# tako.net
KiCad netlist of a schematic drawn in EAGLE
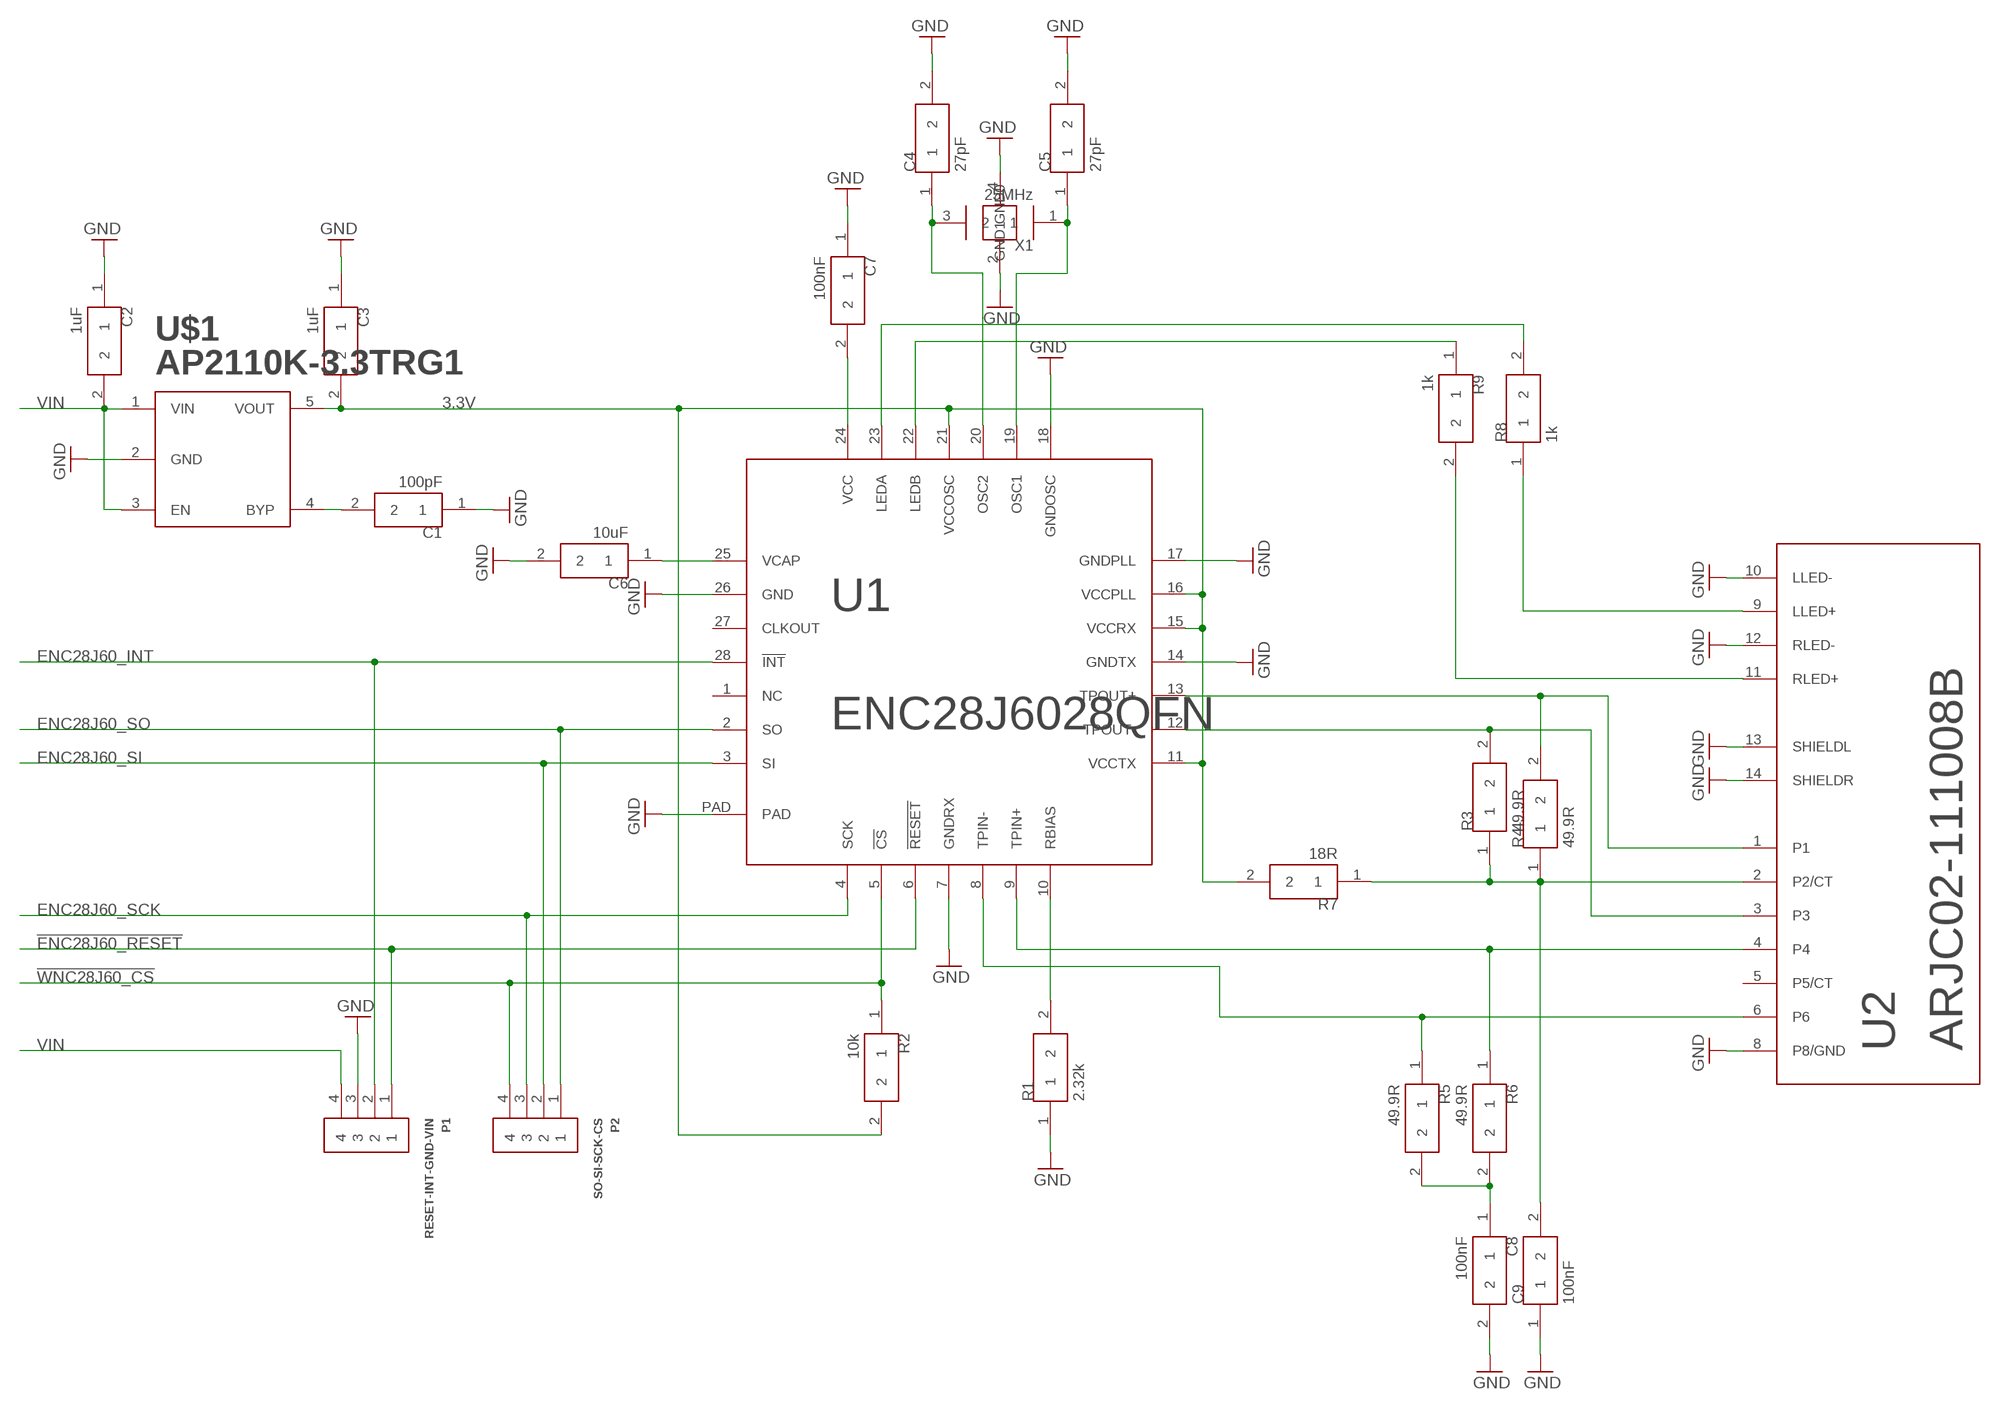
[diagram p0: schematic, sheet 1]

(export (version "E")
  (design (tool "Eeschema 10.0.6"))
  (components
    (comp (ref "C1")
      (value "100pF")
      (footprint "eagle-import:0805")
      (libsource (lib "eagle-import") (part "CAP0805"))
    )
    (comp (ref "C2")
      (value "1uF")
      (footprint "eagle-import:0805")
      (libsource (lib "eagle-import") (part "CAP0805"))
    )
    (comp (ref "C3")
      (value "1uF")
      (footprint "eagle-import:0805")
      (libsource (lib "eagle-import") (part "CAP0805"))
    )
    (comp (ref "C4")
      (value "27pF")
      (footprint "eagle-import:0805")
      (libsource (lib "eagle-import") (part "CAP0805"))
    )
    (comp (ref "C5")
      (value "27pF")
      (footprint "eagle-import:0805")
      (libsource (lib "eagle-import") (part "CAP0805"))
    )
    (comp (ref "C6")
      (value "10uF")
      (footprint "eagle-import:0805")
      (libsource (lib "eagle-import") (part "CAP0805"))
    )
    (comp (ref "C7")
      (value "100nF")
      (footprint "eagle-import:0805")
      (libsource (lib "eagle-import") (part "CAP0805"))
    )
    (comp (ref "C8")
      (value "100nF")
      (footprint "eagle-import:0805")
      (libsource (lib "eagle-import") (part "CAP0805"))
    )
    (comp (ref "C9")
      (value "100nF")
      (footprint "eagle-import:0805")
      (libsource (lib "eagle-import") (part "CAP0805"))
    )
    (comp (ref "P1")
      (value "RESET-INT-GND-VIN")
      (footprint "eagle-import:PIN_4")
      (libsource (lib "eagle-import") (part "PIN_4"))
    )
    (comp (ref "P2")
      (value "SO-SI-SCK-CS")
      (footprint "eagle-import:PIN_4")
      (libsource (lib "eagle-import") (part "PIN_4"))
    )
    (comp (ref "R1")
      (value "2.32k")
      (footprint "eagle-import:0805")
      (libsource (lib "eagle-import") (part "RES0805"))
    )
    (comp (ref "R2")
      (value "10k")
      (footprint "eagle-import:0805")
      (libsource (lib "eagle-import") (part "RES0805"))
    )
    (comp (ref "R3")
      (value "49.9R")
      (footprint "eagle-import:0805")
      (libsource (lib "eagle-import") (part "RES0805"))
    )
    (comp (ref "R4")
      (value "49.9R")
      (footprint "eagle-import:0805")
      (libsource (lib "eagle-import") (part "RES0805"))
    )
    (comp (ref "R5")
      (value "49.9R")
      (footprint "eagle-import:0805")
      (libsource (lib "eagle-import") (part "RES0805"))
    )
    (comp (ref "R6")
      (value "49.9R")
      (footprint "eagle-import:0805")
      (libsource (lib "eagle-import") (part "RES0805"))
    )
    (comp (ref "R7")
      (value "18R")
      (footprint "eagle-import:0805")
      (libsource (lib "eagle-import") (part "RES0805"))
    )
    (comp (ref "R8")
      (value "1k")
      (footprint "eagle-import:0805")
      (libsource (lib "eagle-import") (part "RES0805"))
    )
    (comp (ref "R9")
      (value "1k")
      (footprint "eagle-import:0805")
      (libsource (lib "eagle-import") (part "RES0805"))
    )
    (comp (ref "U$1")
      (value "AP2110K-3.3TRG1")
      (footprint "eagle-import:SOT23-5")
      (libsource (lib "eagle-import") (part "AP2110"))
    )
    (comp (ref "U1")
      (value "ENC28J6028QFN")
      (footprint "eagle-import:28-QFN")
      (libsource (lib "eagle-import") (part "ENC28J6028QFN"))
    )
    (comp (ref "U2")
      (value "ARJC02-111008B")
      (footprint "eagle-import:ARJC02-111008B")
      (libsource (lib "eagle-import") (part "ARJC02-111008B"))
    )
    (comp (ref "X1")
      (value "25MHz")
      (footprint "eagle-import:XTAL_3225")
      (libsource (lib "eagle-import") (part "XTAL_GNDSMD_3225"))
    )
  )
  (nets
    (net (code "1") (name "/3.3V") (class "Default")
      (node (ref "C3") (pin "2") (pinfunction "2_2") (pintype "bidirectional"))
      (node (ref "R2") (pin "2") (pinfunction "2_2") (pintype "bidirectional"))
      (node (ref "R7") (pin "2") (pinfunction "2_2") (pintype "bidirectional"))
      (node (ref "U$1") (pin "5") (pinfunction "VOUT_5") (pintype "bidirectional"))
      (node (ref "U1") (pin "11") (pinfunction "VCCTX_11") (pintype "bidirectional"))
      (node (ref "U1") (pin "15") (pinfunction "VCCRX_15") (pintype "bidirectional"))
      (node (ref "U1") (pin "16") (pinfunction "VCCPLL_16") (pintype "bidirectional"))
      (node (ref "U1") (pin "21") (pinfunction "VCCOSC_21") (pintype "bidirectional"))
    )
    (net (code "2") (name "/ENC28J60_INT") (class "Default")
      (node (ref "P1") (pin "2") (pinfunction "2_2") (pintype "bidirectional"))
      (node (ref "U1") (pin "28") (pinfunction "~{INT}_28") (pintype "bidirectional"))
    )
    (net (code "3") (name "/ENC28J60_SCK") (class "Default")
      (node (ref "P2") (pin "3") (pinfunction "3_3") (pintype "bidirectional"))
      (node (ref "U1") (pin "4") (pinfunction "SCK_4") (pintype "bidirectional"))
    )
    (net (code "4") (name "/ENC28J60_SI") (class "Default")
      (node (ref "P2") (pin "2") (pinfunction "2_2") (pintype "bidirectional"))
      (node (ref "U1") (pin "3") (pinfunction "SI_3") (pintype "bidirectional"))
    )
    (net (code "5") (name "/ENC28J60_SO") (class "Default")
      (node (ref "P2") (pin "1") (pinfunction "1_1") (pintype "bidirectional"))
      (node (ref "U1") (pin "2") (pinfunction "SO_2") (pintype "bidirectional"))
    )
    (net (code "6") (name "/VIN") (class "Default")
      (node (ref "C2") (pin "2") (pinfunction "2_2") (pintype "bidirectional"))
      (node (ref "P1") (pin "4") (pinfunction "4_4") (pintype "bidirectional"))
      (node (ref "U$1") (pin "1") (pinfunction "VIN_1") (pintype "bidirectional"))
      (node (ref "U$1") (pin "3") (pinfunction "EN_3") (pintype "bidirectional"))
    )
    (net (code "7") (name "/~{ENC28J60_RESET}") (class "Default")
      (node (ref "P1") (pin "1") (pinfunction "1_1") (pintype "bidirectional"))
      (node (ref "U1") (pin "6") (pinfunction "~{RESET}_6") (pintype "bidirectional"))
    )
    (net (code "8") (name "/~{WNC28J60_CS}") (class "Default")
      (node (ref "P2") (pin "4") (pinfunction "4_4") (pintype "bidirectional"))
      (node (ref "R2") (pin "1") (pinfunction "1_1") (pintype "bidirectional"))
      (node (ref "U1") (pin "5") (pinfunction "~{CS}_5") (pintype "bidirectional"))
    )
    (net (code "9") (name "GND") (class "Default")
      (node (ref "C1") (pin "1") (pinfunction "1_1") (pintype "bidirectional"))
      (node (ref "C2") (pin "1") (pinfunction "1_1") (pintype "bidirectional"))
      (node (ref "C3") (pin "1") (pinfunction "1_1") (pintype "bidirectional"))
      (node (ref "C4") (pin "2") (pinfunction "2_2") (pintype "bidirectional"))
      (node (ref "C5") (pin "2") (pinfunction "2_2") (pintype "bidirectional"))
      (node (ref "C6") (pin "2") (pinfunction "2_2") (pintype "bidirectional"))
      (node (ref "C7") (pin "1") (pinfunction "1_1") (pintype "bidirectional"))
      (node (ref "C8") (pin "2") (pinfunction "2_2") (pintype "bidirectional"))
      (node (ref "C9") (pin "1") (pinfunction "1_1") (pintype "bidirectional"))
      (node (ref "P1") (pin "3") (pinfunction "3_3") (pintype "bidirectional"))
      (node (ref "R1") (pin "1") (pinfunction "1_1") (pintype "bidirectional"))
      (node (ref "U$1") (pin "2") (pinfunction "GND_2") (pintype "bidirectional"))
      (node (ref "U1") (pin "14") (pinfunction "GNDTX_14") (pintype "bidirectional"))
      (node (ref "U1") (pin "17") (pinfunction "GNDPLL_17") (pintype "bidirectional"))
      (node (ref "U1") (pin "18") (pinfunction "GNDOSC_18") (pintype "bidirectional"))
      (node (ref "U1") (pin "26") (pinfunction "GND_26") (pintype "bidirectional"))
      (node (ref "U1") (pin "7") (pinfunction "GNDRX_7") (pintype "bidirectional"))
      (node (ref "U1") (pin "PAD") (pinfunction "PAD_PAD") (pintype "bidirectional"))
      (node (ref "U2") (pin "10") (pinfunction "LLED-_10") (pintype "bidirectional"))
      (node (ref "U2") (pin "12") (pinfunction "RLED-_12") (pintype "bidirectional"))
      (node (ref "U2") (pin "13") (pinfunction "SHIELDL_13") (pintype "bidirectional"))
      (node (ref "U2") (pin "14") (pinfunction "SHIELDR_14") (pintype "bidirectional"))
      (node (ref "U2") (pin "8") (pinfunction "P8/GND_8") (pintype "bidirectional"))
      (node (ref "X1") (pin "2") (pinfunction "GND0_2") (pintype "bidirectional"))
      (node (ref "X1") (pin "4") (pinfunction "GND1_4") (pintype "bidirectional"))
    )
    (net (code "10") (name "Net-(C8-Pad1)") (class "Default")
      (node (ref "C8") (pin "1") (pinfunction "1_1") (pintype "bidirectional"))
      (node (ref "R5") (pin "2") (pinfunction "2_2") (pintype "bidirectional"))
      (node (ref "R6") (pin "2") (pinfunction "2_2") (pintype "bidirectional"))
    )
    (net (code "11") (name "Net-(U$1-BYP)") (class "Default")
      (node (ref "C1") (pin "2") (pinfunction "2_2") (pintype "bidirectional"))
      (node (ref "U$1") (pin "4") (pinfunction "BYP_4") (pintype "bidirectional"))
    )
    (net (code "12") (name "Net-(U1-LEDA)") (class "Default")
      (node (ref "R8") (pin "2") (pinfunction "2_2") (pintype "bidirectional"))
      (node (ref "U1") (pin "23") (pinfunction "LEDA_23") (pintype "bidirectional"))
    )
    (net (code "13") (name "Net-(U1-LEDB)") (class "Default")
      (node (ref "R9") (pin "1") (pinfunction "1_1") (pintype "bidirectional"))
      (node (ref "U1") (pin "22") (pinfunction "LEDB_22") (pintype "bidirectional"))
    )
    (net (code "14") (name "Net-(U1-OSC1)") (class "Default")
      (node (ref "C5") (pin "1") (pinfunction "1_1") (pintype "bidirectional"))
      (node (ref "U1") (pin "19") (pinfunction "OSC1_19") (pintype "bidirectional"))
      (node (ref "X1") (pin "1") (pinfunction "1_1") (pintype "bidirectional"))
    )
    (net (code "15") (name "Net-(U1-OSC2)") (class "Default")
      (node (ref "C4") (pin "1") (pinfunction "1_1") (pintype "bidirectional"))
      (node (ref "U1") (pin "20") (pinfunction "OSC2_20") (pintype "bidirectional"))
      (node (ref "X1") (pin "3") (pinfunction "2_3") (pintype "bidirectional"))
    )
    (net (code "16") (name "Net-(U1-RBIAS)") (class "Default")
      (node (ref "R1") (pin "2") (pinfunction "2_2") (pintype "bidirectional"))
      (node (ref "U1") (pin "10") (pinfunction "RBIAS_10") (pintype "bidirectional"))
    )
    (net (code "17") (name "Net-(U1-TPIN+)") (class "Default")
      (node (ref "R6") (pin "1") (pinfunction "1_1") (pintype "bidirectional"))
      (node (ref "U1") (pin "9") (pinfunction "TPIN+_9") (pintype "bidirectional"))
      (node (ref "U2") (pin "4") (pinfunction "P4_4") (pintype "bidirectional"))
    )
    (net (code "18") (name "Net-(U1-TPIN-)") (class "Default")
      (node (ref "R5") (pin "1") (pinfunction "1_1") (pintype "bidirectional"))
      (node (ref "U1") (pin "8") (pinfunction "TPIN-_8") (pintype "bidirectional"))
      (node (ref "U2") (pin "6") (pinfunction "P6_6") (pintype "bidirectional"))
    )
    (net (code "19") (name "Net-(U1-TPOUT+)") (class "Default")
      (node (ref "R4") (pin "2") (pinfunction "2_2") (pintype "bidirectional"))
      (node (ref "U1") (pin "13") (pinfunction "TPOUT+_13") (pintype "bidirectional"))
      (node (ref "U2") (pin "1") (pinfunction "P1_1") (pintype "bidirectional"))
    )
    (net (code "20") (name "Net-(U1-TPOUT-)") (class "Default")
      (node (ref "R3") (pin "2") (pinfunction "2_2") (pintype "bidirectional"))
      (node (ref "U1") (pin "12") (pinfunction "TPOUT-_12") (pintype "bidirectional"))
      (node (ref "U2") (pin "3") (pinfunction "P3_3") (pintype "bidirectional"))
    )
    (net (code "21") (name "Net-(U1-VCAP)") (class "Default")
      (node (ref "C6") (pin "1") (pinfunction "1_1") (pintype "bidirectional"))
      (node (ref "U1") (pin "25") (pinfunction "VCAP_25") (pintype "bidirectional"))
    )
    (net (code "22") (name "Net-(U1-VCC)") (class "Default")
      (node (ref "C7") (pin "2") (pinfunction "2_2") (pintype "bidirectional"))
      (node (ref "U1") (pin "24") (pinfunction "VCC_24") (pintype "bidirectional"))
    )
    (net (code "23") (name "Net-(U2-LLED+)") (class "Default")
      (node (ref "R8") (pin "1") (pinfunction "1_1") (pintype "bidirectional"))
      (node (ref "U2") (pin "9") (pinfunction "LLED+_9") (pintype "bidirectional"))
    )
    (net (code "24") (name "Net-(U2-P2{slash}CT)") (class "Default")
      (node (ref "C9") (pin "2") (pinfunction "2_2") (pintype "bidirectional"))
      (node (ref "R3") (pin "1") (pinfunction "1_1") (pintype "bidirectional"))
      (node (ref "R4") (pin "1") (pinfunction "1_1") (pintype "bidirectional"))
      (node (ref "R7") (pin "1") (pinfunction "1_1") (pintype "bidirectional"))
      (node (ref "U2") (pin "2") (pinfunction "P2/CT_2") (pintype "bidirectional"))
    )
    (net (code "25") (name "Net-(U2-RLED+)") (class "Default")
      (node (ref "R9") (pin "2") (pinfunction "2_2") (pintype "bidirectional"))
      (node (ref "U2") (pin "11") (pinfunction "RLED+_11") (pintype "bidirectional"))
    )
    (net (code "26") (name "unconnected-(U1-CLKOUT-Pad27)") (class "Default")
      (node (ref "U1") (pin "27") (pinfunction "CLKOUT_27") (pintype "bidirectional"))
    )
    (net (code "27") (name "unconnected-(U1-NC-Pad1)") (class "Default")
      (node (ref "U1") (pin "1") (pinfunction "NC_1") (pintype "bidirectional"))
    )
    (net (code "28") (name "unconnected-(U2-P5{slash}CT-Pad5)") (class "Default")
      (node (ref "U2") (pin "5") (pinfunction "P5/CT_5") (pintype "bidirectional"))
    )
  )
)
